# USBHeaders.net
KiCad netlist of a schematic drawn in Altium Designer
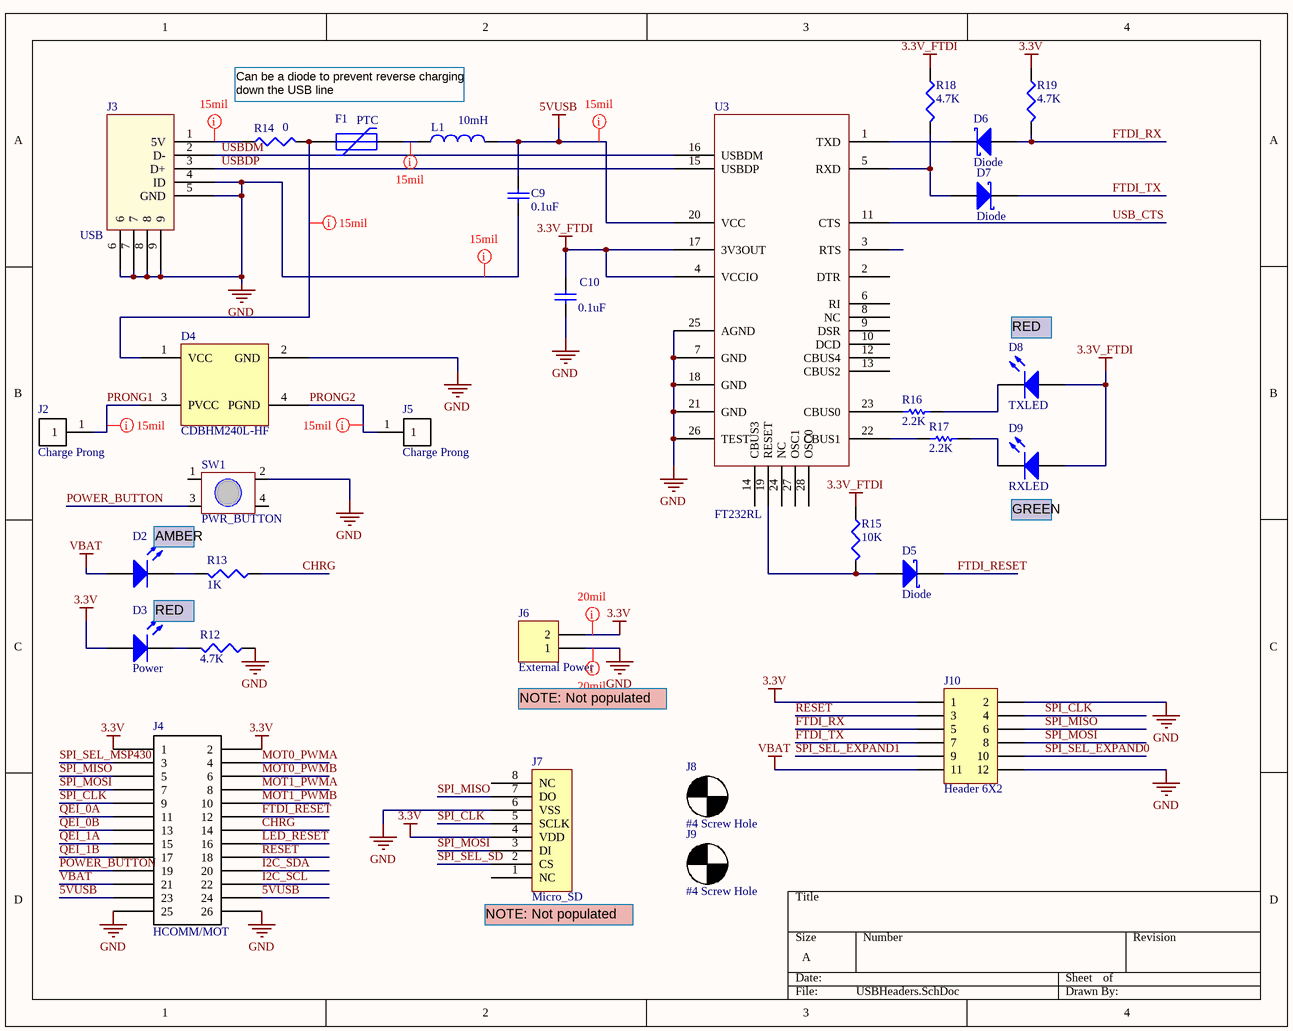
[diagram p0: USBHeaders.SchDoc]

(export (version "E")
  (design (tool "Eeschema 10.0.6"))
  (components
    (comp (ref "C9")
      (value "0.1uF")
      (footprint "CAPC1005L")
      (description "Capacitor")
      (fields (field (name "PUBLISHER") "Altium Limited"))
      (libsource (lib "Miscellaneous Devices") (part "Cap"))
    )
    (comp (ref "C10")
      (value "0.1uF")
      (footprint "CAPC1005L")
      (description "Capacitor")
      (fields (field (name "PUBLISHER") "Altium Limited"))
      (libsource (lib "Miscellaneous Devices") (part "Cap"))
    )
    (comp (ref "D2")
      (value "Charge")
      (footprint "SurfaceMount(603)")
      (description "Typical RED, GREEN, YELLOW, AMBER GaAs LED")
      (fields (field (name "PUBLISHER") "Altium Limited"))
      (libsource (lib "") (part "LED2_1"))
    )
    (comp (ref "D3") (value "Power") (footprint "SurfaceMount(603)") (libsource (lib "mrone") (part "LED")))
    (comp (ref "D4")
      (value "CDBHM240L-HF")
      (footprint "DIODEARRAY_2AMPS")
      (fields (field (name "MPN") "CDBHM240L-HF"))
      (libsource (lib "mrone") (part "DiodeArray2Amps"))
    )
    (comp (ref "D5")
      (value "Diode")
      (footprint "SurfaceMount(603)")
      (libsource (lib "mrone") (part "SchottkeyDiode"))
    )
    (comp (ref "D6")
      (value "Diode")
      (footprint "SurfaceMount(603)")
      (libsource (lib "mrone") (part "SchottkeyDiode"))
    )
    (comp (ref "D7")
      (value "Diode")
      (footprint "SurfaceMount(603)")
      (libsource (lib "mrone") (part "SchottkeyDiode"))
    )
    (comp (ref "D8")
      (value "TXLED")
      (footprint "SurfaceMount(603)")
      (description "Typical RED, GREEN, YELLOW, AMBER GaAs LED")
      (fields (field (name "PUBLISHER") "Altium Limited"))
      (libsource (lib "Miscellaneous Devices") (part "LED2"))
    )
    (comp (ref "D9")
      (value "RXLED")
      (footprint "SurfaceMount(603)")
      (description "Typical RED, GREEN, YELLOW, AMBER GaAs LED")
      (fields (field (name "PUBLISHER") "Altium Limited"))
      (libsource (lib "Miscellaneous Devices") (part "LED2"))
    )
    (comp (ref "F1")
      (value "PTC")
      (footprint "ERJ8G-1206")
      (description "Fuse")
      (fields (field (name "PUBLISHER") "Altium Limited"))
      (libsource (lib "mrone") (part "PTC_FUSE"))
    )
    (comp (ref "J2")
      (value "Charge Prong")
      (footprint "CHARGING_PRONG")
      (description "Charging Prong Hole with Plating")
      (libsource (lib "mrone") (part "CHARGE_PRONG"))
    )
    (comp (ref "J3")
      (value "USB")
      (footprint "USB Minib (thru-hole)")
      (libsource (lib "mrone") (part "USB-ConnTH"))
    )
    (comp (ref "J4")
      (value "HCOMM/MOT")
      (footprint "HeaderSM 13x2")
      (description "Header, 2X20, 50mil, IDC")
      (libsource (lib "mrone") (part "HCOMM/HMOT"))
    )
    (comp (ref "J5")
      (value "Charge Prong")
      (footprint "CHARGING_PRONG")
      (description "Charging Prong Hole with Plating")
      (libsource (lib "mrone") (part "CHARGE_PRONG"))
    )
    (comp (ref "J6")
      (value "External Power")
      (footprint "HDR1X2")
      (description "Header, 2-Pin")
      (fields (field (name "PUBLISHER") "Altium Limited"))
      (libsource (lib "Miscellaneous Connectors") (part "Header 2"))
    )
    (comp (ref "J7") (value "Micro_SD") (footprint "MICRO_SD") (libsource (lib "mrone") (part "MICRO_SD")))
    (comp (ref "J8")
      (value "#4 Screw Hole")
      (footprint "#4_Screw_Hole")
      (description "A mechanical hole for mounting the board")
      (libsource (lib "mrone") (part "Mechanical_Hole"))
    )
    (comp (ref "J9")
      (value "#4 Screw Hole")
      (footprint "#4_Screw_Hole")
      (description "A mechanical hole for mounting the board")
      (libsource (lib "mrone") (part "Mechanical_Hole"))
    )
    (comp (ref "J10")
      (value "Header 6X2")
      (footprint "HDR2X6")
      (description "Header, 6-Pin, Dual row")
      (fields (field (name "PUBLISHER") "Altium Limited"))
      (libsource (lib "Miscellaneous Connectors") (part "Header 6X2"))
    )
    (comp (ref "L1")
      (value "10mH")
      (footprint "INDC2012L")
      (description "Inductor")
      (fields (field (name "PUBLISHER") "Altium Limited"))
      (libsource (lib "Miscellaneous Devices") (part "Inductor"))
    )
    (comp (ref "R12")
      (value "4.7K")
      (footprint "RESC1608L")
      (description "Resistor")
      (fields (field (name "Comment") "Res3") (field (name "PUBLISHER") "Altium Limited"))
      (libsource (lib "Miscellaneous Devices") (part "Res3"))
    )
    (comp (ref "R13")
      (value "1K")
      (footprint "RESC1608L")
      (description "Resistor")
      (fields (field (name "Comment") "Res3") (field (name "PUBLISHER") "Altium Limited"))
      (libsource (lib "Miscellaneous Devices") (part "Res3"))
    )
    (comp (ref "R14")
      (value "0")
      (footprint "RESC1608L")
      (description "Resistor")
      (fields (field (name "Comment") "Res3") (field (name "PUBLISHER") "Altium Limited"))
      (libsource (lib "Miscellaneous Devices") (part "Res3"))
    )
    (comp (ref "R15")
      (value "10K")
      (footprint "RESC1608L")
      (description "Resistor")
      (fields (field (name "Comment") "Res3") (field (name "PUBLISHER") "Altium Limited"))
      (libsource (lib "Miscellaneous Devices") (part "Res3"))
    )
    (comp (ref "R16")
      (value "2.2K")
      (footprint "RESC1608L")
      (description "Resistor")
      (fields (field (name "PUBLISHER") "Altium Limited"))
      (libsource (lib "Miscellaneous Devices") (part "Res1"))
    )
    (comp (ref "R17")
      (value "2.2K")
      (footprint "RESC1608L")
      (description "Resistor")
      (fields (field (name "PUBLISHER") "Altium Limited"))
      (libsource (lib "Miscellaneous Devices") (part "Res1"))
    )
    (comp (ref "R18")
      (value "4.7K")
      (footprint "RESC1608L")
      (description "Resistor")
      (fields (field (name "Comment") "Res3") (field (name "PUBLISHER") "Altium Limited"))
      (libsource (lib "Miscellaneous Devices") (part "Res3"))
    )
    (comp (ref "R19")
      (value "4.7K")
      (footprint "RESC1608L")
      (description "Resistor")
      (fields (field (name "Comment") "Res3") (field (name "PUBLISHER") "Altium Limited"))
      (libsource (lib "Miscellaneous Devices") (part "Res3"))
    )
    (comp (ref "SW1")
      (value "PWR_BUTTON")
      (footprint "SwitchTall-TL330")
      (libsource (lib "mrone") (part "Switch-TL330"))
    )
    (comp (ref "U3") (value "FT232RL") (footprint "SSOP-28") (libsource (lib "mrone") (part "FT232RL")))
  )
  (nets
    (net (code "2") (name "/CHRG") (class "Default")
      (node (ref "J4") (pin "14") (pinfunction "14_14") (pintype "passive"))
      (node (ref "R13") (pin "1") (pinfunction "1_1") (pintype "passive"))
    )
    (net (code "3") (name "/FTDI_RESET") (class "Default")
      (node (ref "D5") (pin "1") (pinfunction "K_1") (pintype "passive"))
      (node (ref "J4") (pin "12") (pinfunction "12_12") (pintype "passive"))
    )
    (net (code "4") (name "/FTDI_RX") (class "Default")
      (node (ref "D6") (pin "2") (pinfunction "A_2") (pintype "passive"))
      (node (ref "J10") (pin "5") (pinfunction "5_5") (pintype "passive"))
      (node (ref "R19") (pin "2") (pinfunction "2_2") (pintype "passive"))
    )
    (net (code "5") (name "/FTDI_TX") (class "Default")
      (node (ref "D7") (pin "1") (pinfunction "K_1") (pintype "passive"))
      (node (ref "J10") (pin "7") (pinfunction "7_7") (pintype "passive"))
    )
    (net (code "6") (name "/I2C_SCL") (class "Default")
      (node (ref "J4") (pin "22") (pinfunction "22_22") (pintype "passive"))
    )
    (net (code "7") (name "/I2C_SDA") (class "Default")
      (node (ref "J4") (pin "20") (pinfunction "20_20") (pintype "passive"))
    )
    (net (code "8") (name "/LED_RESET") (class "Default")
      (node (ref "J4") (pin "16") (pinfunction "16_16") (pintype "passive"))
    )
    (net (code "9") (name "/MOT0_PWMA") (class "Default")
      (node (ref "J4") (pin "4") (pinfunction "4_4") (pintype "passive"))
    )
    (net (code "10") (name "/MOT0_PWMB") (class "Default")
      (node (ref "J4") (pin "6") (pinfunction "6_6") (pintype "passive"))
    )
    (net (code "11") (name "/MOT1_PWMA") (class "Default")
      (node (ref "J4") (pin "8") (pinfunction "8_8") (pintype "passive"))
    )
    (net (code "12") (name "/MOT1_PWMB") (class "Default")
      (node (ref "J4") (pin "10") (pinfunction "10_10") (pintype "passive"))
    )
    (net (code "13") (name "/POWER_BUTTON") (class "Default")
      (node (ref "J4") (pin "19") (pinfunction "19_19") (pintype "passive"))
      (node (ref "SW1") (pin "3") (pinfunction "3_3") (pintype "passive"))
    )
    (net (code "14") (name "/PRONG1") (class "Default")
      (node (ref "D4") (pin "3") (pinfunction "PVCC_3") (pintype "passive"))
      (node (ref "J2") (pin "1") (pinfunction "1_1") (pintype "passive"))
    )
    (net (code "15") (name "/PRONG2") (class "Default")
      (node (ref "D4") (pin "4") (pinfunction "PGND_4") (pintype "passive"))
      (node (ref "J5") (pin "1") (pinfunction "1_1") (pintype "passive"))
    )
    (net (code "16") (name "/QEI_0A") (class "Default")
      (node (ref "J4") (pin "11") (pinfunction "11_11") (pintype "passive"))
    )
    (net (code "17") (name "/QEI_0B") (class "Default")
      (node (ref "J4") (pin "13") (pinfunction "13_13") (pintype "passive"))
    )
    (net (code "18") (name "/QEI_1A") (class "Default")
      (node (ref "J4") (pin "15") (pinfunction "15_15") (pintype "passive"))
    )
    (net (code "19") (name "/QEI_1B") (class "Default")
      (node (ref "J4") (pin "17") (pinfunction "17_17") (pintype "passive"))
    )
    (net (code "20") (name "/RESET") (class "Default")
      (node (ref "J10") (pin "3") (pinfunction "3_3") (pintype "passive"))
      (node (ref "J4") (pin "18") (pinfunction "18_18") (pintype "passive"))
    )
    (net (code "21") (name "/SPI_CLK") (class "Default")
      (node (ref "J10") (pin "4") (pinfunction "4_4") (pintype "passive"))
      (node (ref "J4") (pin "9") (pinfunction "9_9") (pintype "passive"))
      (node (ref "J7") (pin "5") (pinfunction "SCLK_5") (pintype "passive"))
    )
    (net (code "22") (name "/SPI_MISO") (class "Default")
      (node (ref "J10") (pin "6") (pinfunction "6_6") (pintype "passive"))
      (node (ref "J4") (pin "5") (pinfunction "5_5") (pintype "passive"))
      (node (ref "J7") (pin "7") (pinfunction "DO_7") (pintype "passive"))
    )
    (net (code "23") (name "/SPI_MOSI") (class "Default")
      (node (ref "J10") (pin "8") (pinfunction "8_8") (pintype "passive"))
      (node (ref "J4") (pin "7") (pinfunction "7_7") (pintype "passive"))
      (node (ref "J7") (pin "3") (pinfunction "DI_3") (pintype "passive"))
    )
    (net (code "24") (name "/SPI_SEL_EXPAND0") (class "Default")
      (node (ref "J10") (pin "10") (pinfunction "10_10") (pintype "passive"))
    )
    (net (code "25") (name "/SPI_SEL_EXPAND1") (class "Default")
      (node (ref "J10") (pin "9") (pinfunction "9_9") (pintype "passive"))
    )
    (net (code "26") (name "/SPI_SEL_MSP430") (class "Default")
      (node (ref "J4") (pin "3") (pinfunction "3_3") (pintype "passive"))
    )
    (net (code "27") (name "/SPI_SEL_SD") (class "Default")
      (node (ref "J7") (pin "2") (pinfunction "CS_2") (pintype "passive"))
    )
    (net (code "28") (name "/USBDM") (class "Default")
      (node (ref "J3") (pin "2") (pinfunction "D-_2") (pintype "passive"))
      (node (ref "U3") (pin "16") (pinfunction "USBDM_16") (pintype "passive"))
    )
    (net (code "29") (name "/USBDP") (class "Default")
      (node (ref "J3") (pin "3") (pinfunction "D+_3") (pintype "passive"))
      (node (ref "U3") (pin "15") (pinfunction "USBDP_15") (pintype "passive"))
    )
    (net (code "30") (name "/USB_CTS") (class "Default")
      (node (ref "U3") (pin "11") (pinfunction "CTS_11") (pintype "passive"))
    )
    (net (code "31") (name "3.3V") (class "Default")
      (node (ref "D3") (pin "1") (pinfunction "A_1") (pintype "passive"))
      (node (ref "J10") (pin "1") (pinfunction "1_1") (pintype "passive"))
      (node (ref "J4") (pin "1") (pinfunction "1_1") (pintype "passive"))
      (node (ref "J4") (pin "2") (pinfunction "2_2") (pintype "passive"))
      (node (ref "J6") (pin "2") (pinfunction "2_2") (pintype "passive"))
      (node (ref "J7") (pin "4") (pinfunction "VDD_4") (pintype "passive"))
      (node (ref "R19") (pin "1") (pinfunction "1_1") (pintype "passive"))
    )
    (net (code "32") (name "3.3V_FTDI") (class "Default")
      (node (ref "C10") (pin "2") (pinfunction "2_2") (pintype "passive"))
      (node (ref "D8") (pin "1") (pinfunction "A_1") (pintype "passive"))
      (node (ref "D9") (pin "1") (pinfunction "A_1") (pintype "passive"))
      (node (ref "R15") (pin "1") (pinfunction "1_1") (pintype "passive"))
      (node (ref "R18") (pin "1") (pinfunction "1_1") (pintype "passive"))
      (node (ref "U3") (pin "17") (pinfunction "3V3OUT_17") (pintype "passive"))
      (node (ref "U3") (pin "4") (pinfunction "VCCIO_4") (pintype "passive"))
    )
    (net (code "33") (name "5VUSB") (class "Default")
      (node (ref "C9") (pin "2") (pinfunction "2_2") (pintype "passive"))
      (node (ref "J4") (pin "23") (pinfunction "23_23") (pintype "passive"))
      (node (ref "J4") (pin "24") (pinfunction "24_24") (pintype "passive"))
      (node (ref "L1") (pin "2") (pinfunction "2_2") (pintype "passive"))
      (node (ref "U3") (pin "20") (pinfunction "VCC_20") (pintype "passive"))
    )
    (net (code "34") (name "GND") (class "Default")
      (node (ref "C10") (pin "1") (pinfunction "1_1") (pintype "passive"))
      (node (ref "C9") (pin "1") (pinfunction "1_1") (pintype "passive"))
      (node (ref "D4") (pin "2") (pinfunction "GND_2") (pintype "passive"))
      (node (ref "J10") (pin "12") (pinfunction "12_12") (pintype "passive"))
      (node (ref "J10") (pin "2") (pinfunction "2_2") (pintype "passive"))
      (node (ref "J3") (pin "4") (pinfunction "ID_4") (pintype "passive"))
      (node (ref "J3") (pin "5") (pinfunction "GND_5") (pintype "passive"))
      (node (ref "J3") (pin "6") (pinfunction "6_6") (pintype "passive"))
      (node (ref "J3") (pin "7") (pinfunction "7_7") (pintype "passive"))
      (node (ref "J3") (pin "8") (pinfunction "8_8") (pintype "passive"))
      (node (ref "J3") (pin "9") (pinfunction "9_9") (pintype "passive"))
      (node (ref "J4") (pin "25") (pinfunction "25_25") (pintype "passive"))
      (node (ref "J4") (pin "26") (pinfunction "26_26") (pintype "passive"))
      (node (ref "J6") (pin "1") (pinfunction "1_1") (pintype "passive"))
      (node (ref "J7") (pin "6") (pinfunction "VSS_6") (pintype "passive"))
      (node (ref "R12") (pin "1") (pinfunction "1_1") (pintype "passive"))
      (node (ref "SW1") (pin "2") (pinfunction "2_2") (pintype "passive"))
      (node (ref "U3") (pin "18") (pinfunction "GND_18") (pintype "passive"))
      (node (ref "U3") (pin "21") (pinfunction "GND_21") (pintype "passive"))
      (node (ref "U3") (pin "25") (pinfunction "AGND_25") (pintype "passive"))
      (node (ref "U3") (pin "26") (pinfunction "TEST_26") (pintype "passive"))
      (node (ref "U3") (pin "7") (pinfunction "GND_7") (pintype "passive"))
    )
    (net (code "35") (name "Net-(D2-K)") (class "Default")
      (node (ref "D2") (pin "2") (pinfunction "K_2") (pintype "passive"))
      (node (ref "R13") (pin "2") (pinfunction "2_2") (pintype "passive"))
    )
    (net (code "36") (name "Net-(D3-K)") (class "Default")
      (node (ref "D3") (pin "2") (pinfunction "K_2") (pintype "passive"))
      (node (ref "R12") (pin "2") (pinfunction "2_2") (pintype "passive"))
    )
    (net (code "37") (name "Net-(D4-VCC)") (class "Default")
      (node (ref "D4") (pin "1") (pinfunction "VCC_1") (pintype "passive"))
      (node (ref "F1") (pin "2") (pinfunction "2_2") (pintype "passive"))
      (node (ref "R14") (pin "2") (pinfunction "2_2") (pintype "passive"))
    )
    (net (code "38") (name "Net-(D5-A)") (class "Default")
      (node (ref "D5") (pin "2") (pinfunction "A_2") (pintype "passive"))
      (node (ref "R15") (pin "2") (pinfunction "2_2") (pintype "passive"))
      (node (ref "U3") (pin "19") (pinfunction "RESET_19") (pintype "passive"))
    )
    (net (code "39") (name "Net-(D6-K)") (class "Default")
      (node (ref "D6") (pin "1") (pinfunction "K_1") (pintype "passive"))
      (node (ref "U3") (pin "1") (pinfunction "TXD_1") (pintype "passive"))
    )
    (net (code "40") (name "Net-(D7-A)") (class "Default")
      (node (ref "D7") (pin "2") (pinfunction "A_2") (pintype "passive"))
      (node (ref "R18") (pin "2") (pinfunction "2_2") (pintype "passive"))
      (node (ref "U3") (pin "5") (pinfunction "RXD_5") (pintype "passive"))
    )
    (net (code "41") (name "Net-(D8-K)") (class "Default")
      (node (ref "D8") (pin "2") (pinfunction "K_2") (pintype "passive"))
      (node (ref "R16") (pin "2") (pinfunction "2_2") (pintype "passive"))
    )
    (net (code "42") (name "Net-(D9-K)") (class "Default")
      (node (ref "D9") (pin "2") (pinfunction "K_2") (pintype "passive"))
      (node (ref "R17") (pin "2") (pinfunction "2_2") (pintype "passive"))
    )
    (net (code "43") (name "Net-(F1-Pad1)") (class "Default")
      (node (ref "F1") (pin "1") (pinfunction "1_1") (pintype "passive"))
      (node (ref "L1") (pin "1") (pinfunction "1_1") (pintype "passive"))
    )
    (net (code "44") (name "Net-(J3-5V)") (class "Default")
      (node (ref "J3") (pin "1") (pinfunction "5V_1") (pintype "passive"))
      (node (ref "R14") (pin "1") (pinfunction "1_1") (pintype "passive"))
    )
    (net (code "45") (name "Net-(U3-CBUS0)") (class "Default")
      (node (ref "R16") (pin "1") (pinfunction "1_1") (pintype "passive"))
      (node (ref "U3") (pin "23") (pinfunction "CBUS0_23") (pintype "passive"))
    )
    (net (code "46") (name "Net-(U3-CBUS1)") (class "Default")
      (node (ref "R17") (pin "1") (pinfunction "1_1") (pintype "passive"))
      (node (ref "U3") (pin "22") (pinfunction "CBUS1_22") (pintype "passive"))
    )
    (net (code "47") (name "VBAT") (class "Default")
      (node (ref "D2") (pin "1") (pinfunction "A_1") (pintype "passive"))
      (node (ref "J10") (pin "11") (pinfunction "11_11") (pintype "passive"))
      (node (ref "J4") (pin "21") (pinfunction "21_21") (pintype "passive"))
    )
    (net (code "48") (name "unconnected-(J7-NC-Pad1)") (class "Default")
      (node (ref "J7") (pin "1") (pinfunction "NC_1") (pintype "passive"))
    )
    (net (code "49") (name "unconnected-(J7-NC-Pad8)") (class "Default")
      (node (ref "J7") (pin "8") (pinfunction "NC_8") (pintype "passive"))
    )
    (net (code "50") (name "unconnected-(SW1-Pad1)") (class "Default")
      (node (ref "SW1") (pin "1") (pinfunction "1_1") (pintype "passive"))
    )
    (net (code "51") (name "unconnected-(SW1-Pad4)") (class "Default")
      (node (ref "SW1") (pin "4") (pinfunction "4_4") (pintype "passive"))
    )
    (net (code "52") (name "unconnected-(U3-CBUS2-Pad13)") (class "Default")
      (node (ref "U3") (pin "13") (pinfunction "CBUS2_13") (pintype "passive"))
    )
    (net (code "53") (name "unconnected-(U3-CBUS3-Pad14)") (class "Default")
      (node (ref "U3") (pin "14") (pinfunction "CBUS3_14") (pintype "passive"))
    )
    (net (code "54") (name "unconnected-(U3-CBUS4-Pad12)") (class "Default")
      (node (ref "U3") (pin "12") (pinfunction "CBUS4_12") (pintype "passive"))
    )
    (net (code "55") (name "unconnected-(U3-DCD-Pad10)") (class "Default")
      (node (ref "U3") (pin "10") (pinfunction "DCD_10") (pintype "passive"))
    )
    (net (code "56") (name "unconnected-(U3-DSR-Pad9)") (class "Default")
      (node (ref "U3") (pin "9") (pinfunction "DSR_9") (pintype "passive"))
    )
    (net (code "57") (name "unconnected-(U3-DTR-Pad2)") (class "Default")
      (node (ref "U3") (pin "2") (pinfunction "DTR_2") (pintype "passive"))
    )
    (net (code "58") (name "unconnected-(U3-NC-Pad8)") (class "Default")
      (node (ref "U3") (pin "8") (pinfunction "NC_8") (pintype "passive"))
    )
    (net (code "59") (name "unconnected-(U3-NC-Pad24)") (class "Default")
      (node (ref "U3") (pin "24") (pinfunction "NC_24") (pintype "passive"))
    )
    (net (code "60") (name "unconnected-(U3-OSC0-Pad28)") (class "Default")
      (node (ref "U3") (pin "28") (pinfunction "OSC0_28") (pintype "passive"))
    )
    (net (code "61") (name "unconnected-(U3-OSC1-Pad27)") (class "Default")
      (node (ref "U3") (pin "27") (pinfunction "OSC1_27") (pintype "passive"))
    )
    (net (code "62") (name "unconnected-(U3-RI-Pad6)") (class "Default")
      (node (ref "U3") (pin "6") (pinfunction "RI_6") (pintype "passive"))
    )
    (net (code "63") (name "unconnected-(U3-RTS-Pad3)") (class "Default")
      (node (ref "U3") (pin "3") (pinfunction "RTS_3") (pintype "passive"))
    )
  )
)
